# Main.net
KiCad netlist of a schematic drawn in Altium Designer
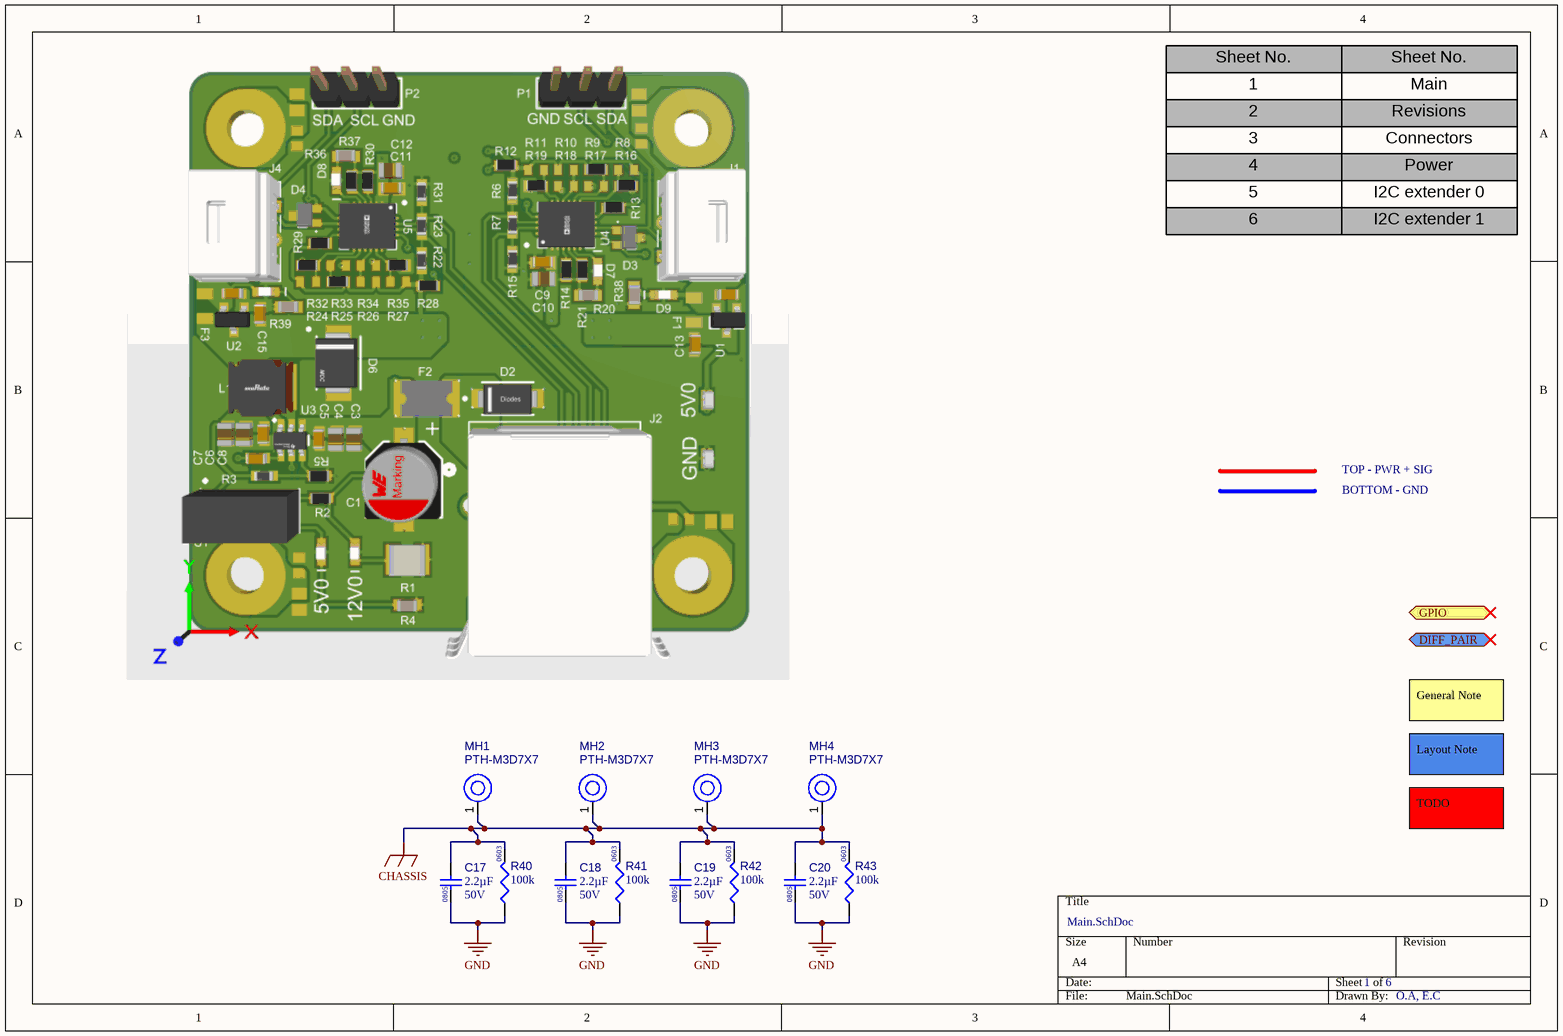
[diagram p0: Main.SchDoc]

(export (version "E")
  (design (tool "Eeschema 10.0.6"))
  (components
    (comp (ref "C17")
      (value "2.2µF")
      (footprint "FP-CL21-IPC_C")
      (fields
        (field (name "RATED DC VOLTAGE (URDC)") "50V")
        (field (name "CASE/PACKAGE") "0805")
        (field (name "Comment") "CL21A225KBFNNNE")
      )
      (libsource (lib "hawaiirobotics") (part "CAP-NP-2"))
    )
    (comp (ref "C18")
      (value "2.2µF")
      (footprint "FP-CL21-IPC_C")
      (fields
        (field (name "RATED DC VOLTAGE (URDC)") "50V")
        (field (name "CASE/PACKAGE") "0805")
        (field (name "Comment") "CL21A225KBFNNNE")
      )
      (libsource (lib "hawaiirobotics") (part "CAP-NP-2"))
    )
    (comp (ref "C19")
      (value "2.2µF")
      (footprint "FP-CL21-IPC_C")
      (fields
        (field (name "RATED DC VOLTAGE (URDC)") "50V")
        (field (name "CASE/PACKAGE") "0805")
        (field (name "Comment") "CL21A225KBFNNNE")
      )
      (libsource (lib "hawaiirobotics") (part "CAP-NP-2"))
    )
    (comp (ref "C20")
      (value "2.2µF")
      (footprint "FP-CL21-IPC_C")
      (fields
        (field (name "RATED DC VOLTAGE (URDC)") "50V")
        (field (name "CASE/PACKAGE") "0805")
        (field (name "Comment") "CL21A225KBFNNNE")
      )
      (libsource (lib "hawaiirobotics") (part "CAP-NP-2"))
    )
    (comp (ref "MH1")
      (value "PTH-M3D7X7")
      (footprint "PTH-M2D5X5")
      (description "M3 PTH (3.3mm), 7mm pad")
      (libsource (lib "hawaiirobotics") (part "CMP-00028-00000-1"))
    )
    (comp (ref "MH2")
      (value "PTH-M3D7X7")
      (footprint "PTH-M2D5X5")
      (description "M3 PTH (3.3mm), 7mm pad")
      (libsource (lib "hawaiirobotics") (part "CMP-00028-00000-1"))
    )
    (comp (ref "MH3")
      (value "PTH-M3D7X7")
      (footprint "PTH-M2D5X5")
      (description "M3 PTH (3.3mm), 7mm pad")
      (libsource (lib "hawaiirobotics") (part "CMP-00028-00000-1"))
    )
    (comp (ref "MH4")
      (value "PTH-M3D7X7")
      (footprint "PTH-M2D5X5")
      (description "M3 PTH (3.3mm), 7mm pad")
      (libsource (lib "hawaiirobotics") (part "CMP-00028-00000-1"))
    )
    (comp (ref "R40")
      (value "100k")
      (footprint "RESC1608X55X25NL10T15")
      (fields
        (field (name "POWER") "100mW")
        (field (name "TOLERANCE") "1%")
        (field (name "CASE/PACKAGE") "0603")
        (field (name "Comment") "RC0603FR-07100KL")
      )
      (libsource (lib "hawaiirobotics") (part "RES-2"))
    )
    (comp (ref "R41")
      (value "100k")
      (footprint "RESC1608X55X25NL10T15")
      (fields
        (field (name "POWER") "100mW")
        (field (name "TOLERANCE") "1%")
        (field (name "CASE/PACKAGE") "0603")
        (field (name "Comment") "RC0603FR-07100KL")
      )
      (libsource (lib "hawaiirobotics") (part "RES-2"))
    )
    (comp (ref "R42")
      (value "100k")
      (footprint "RESC1608X55X25NL10T15")
      (fields
        (field (name "POWER") "100mW")
        (field (name "TOLERANCE") "1%")
        (field (name "CASE/PACKAGE") "0603")
        (field (name "Comment") "RC0603FR-07100KL")
      )
      (libsource (lib "hawaiirobotics") (part "RES-2"))
    )
    (comp (ref "R43")
      (value "100k")
      (footprint "RESC1608X55X25NL10T15")
      (fields
        (field (name "POWER") "100mW")
        (field (name "TOLERANCE") "1%")
        (field (name "CASE/PACKAGE") "0603")
        (field (name "Comment") "RC0603FR-07100KL")
      )
      (libsource (lib "hawaiirobotics") (part "RES-2"))
    )
  )
  (nets
    (net (code "3") (name "CHASSIS") (class "Default")
      (node (ref "C17") (pin "2") (pinfunction "2_2") (pintype "passive"))
      (node (ref "C18") (pin "2") (pinfunction "2_2") (pintype "passive"))
      (node (ref "C19") (pin "2") (pinfunction "2_2") (pintype "passive"))
      (node (ref "C20") (pin "2") (pinfunction "2_2") (pintype "passive"))
      (node (ref "MH1") (pin "1") (pinfunction "H1_1") (pintype "passive"))
      (node (ref "MH2") (pin "1") (pinfunction "H1_1") (pintype "passive"))
      (node (ref "MH3") (pin "1") (pinfunction "H1_1") (pintype "passive"))
      (node (ref "MH4") (pin "1") (pinfunction "H1_1") (pintype "passive"))
      (node (ref "R40") (pin "2") (pinfunction "2_2") (pintype "passive"))
      (node (ref "R41") (pin "2") (pinfunction "2_2") (pintype "passive"))
      (node (ref "R42") (pin "2") (pinfunction "2_2") (pintype "passive"))
      (node (ref "R43") (pin "2") (pinfunction "2_2") (pintype "passive"))
    )
    (net (code "4") (name "GND") (class "Default")
      (node (ref "C17") (pin "1") (pinfunction "1_1") (pintype "passive"))
      (node (ref "C18") (pin "1") (pinfunction "1_1") (pintype "passive"))
      (node (ref "C19") (pin "1") (pinfunction "1_1") (pintype "passive"))
      (node (ref "C20") (pin "1") (pinfunction "1_1") (pintype "passive"))
      (node (ref "R40") (pin "1") (pinfunction "1_1") (pintype "passive"))
      (node (ref "R41") (pin "1") (pinfunction "1_1") (pintype "passive"))
      (node (ref "R42") (pin "1") (pinfunction "1_1") (pintype "passive"))
      (node (ref "R43") (pin "1") (pinfunction "1_1") (pintype "passive"))
    )
  )
)
